# CAMERA_DVP_FPC24_OV26407670.net
KiCad netlist of a schematic drawn in Altium Designer
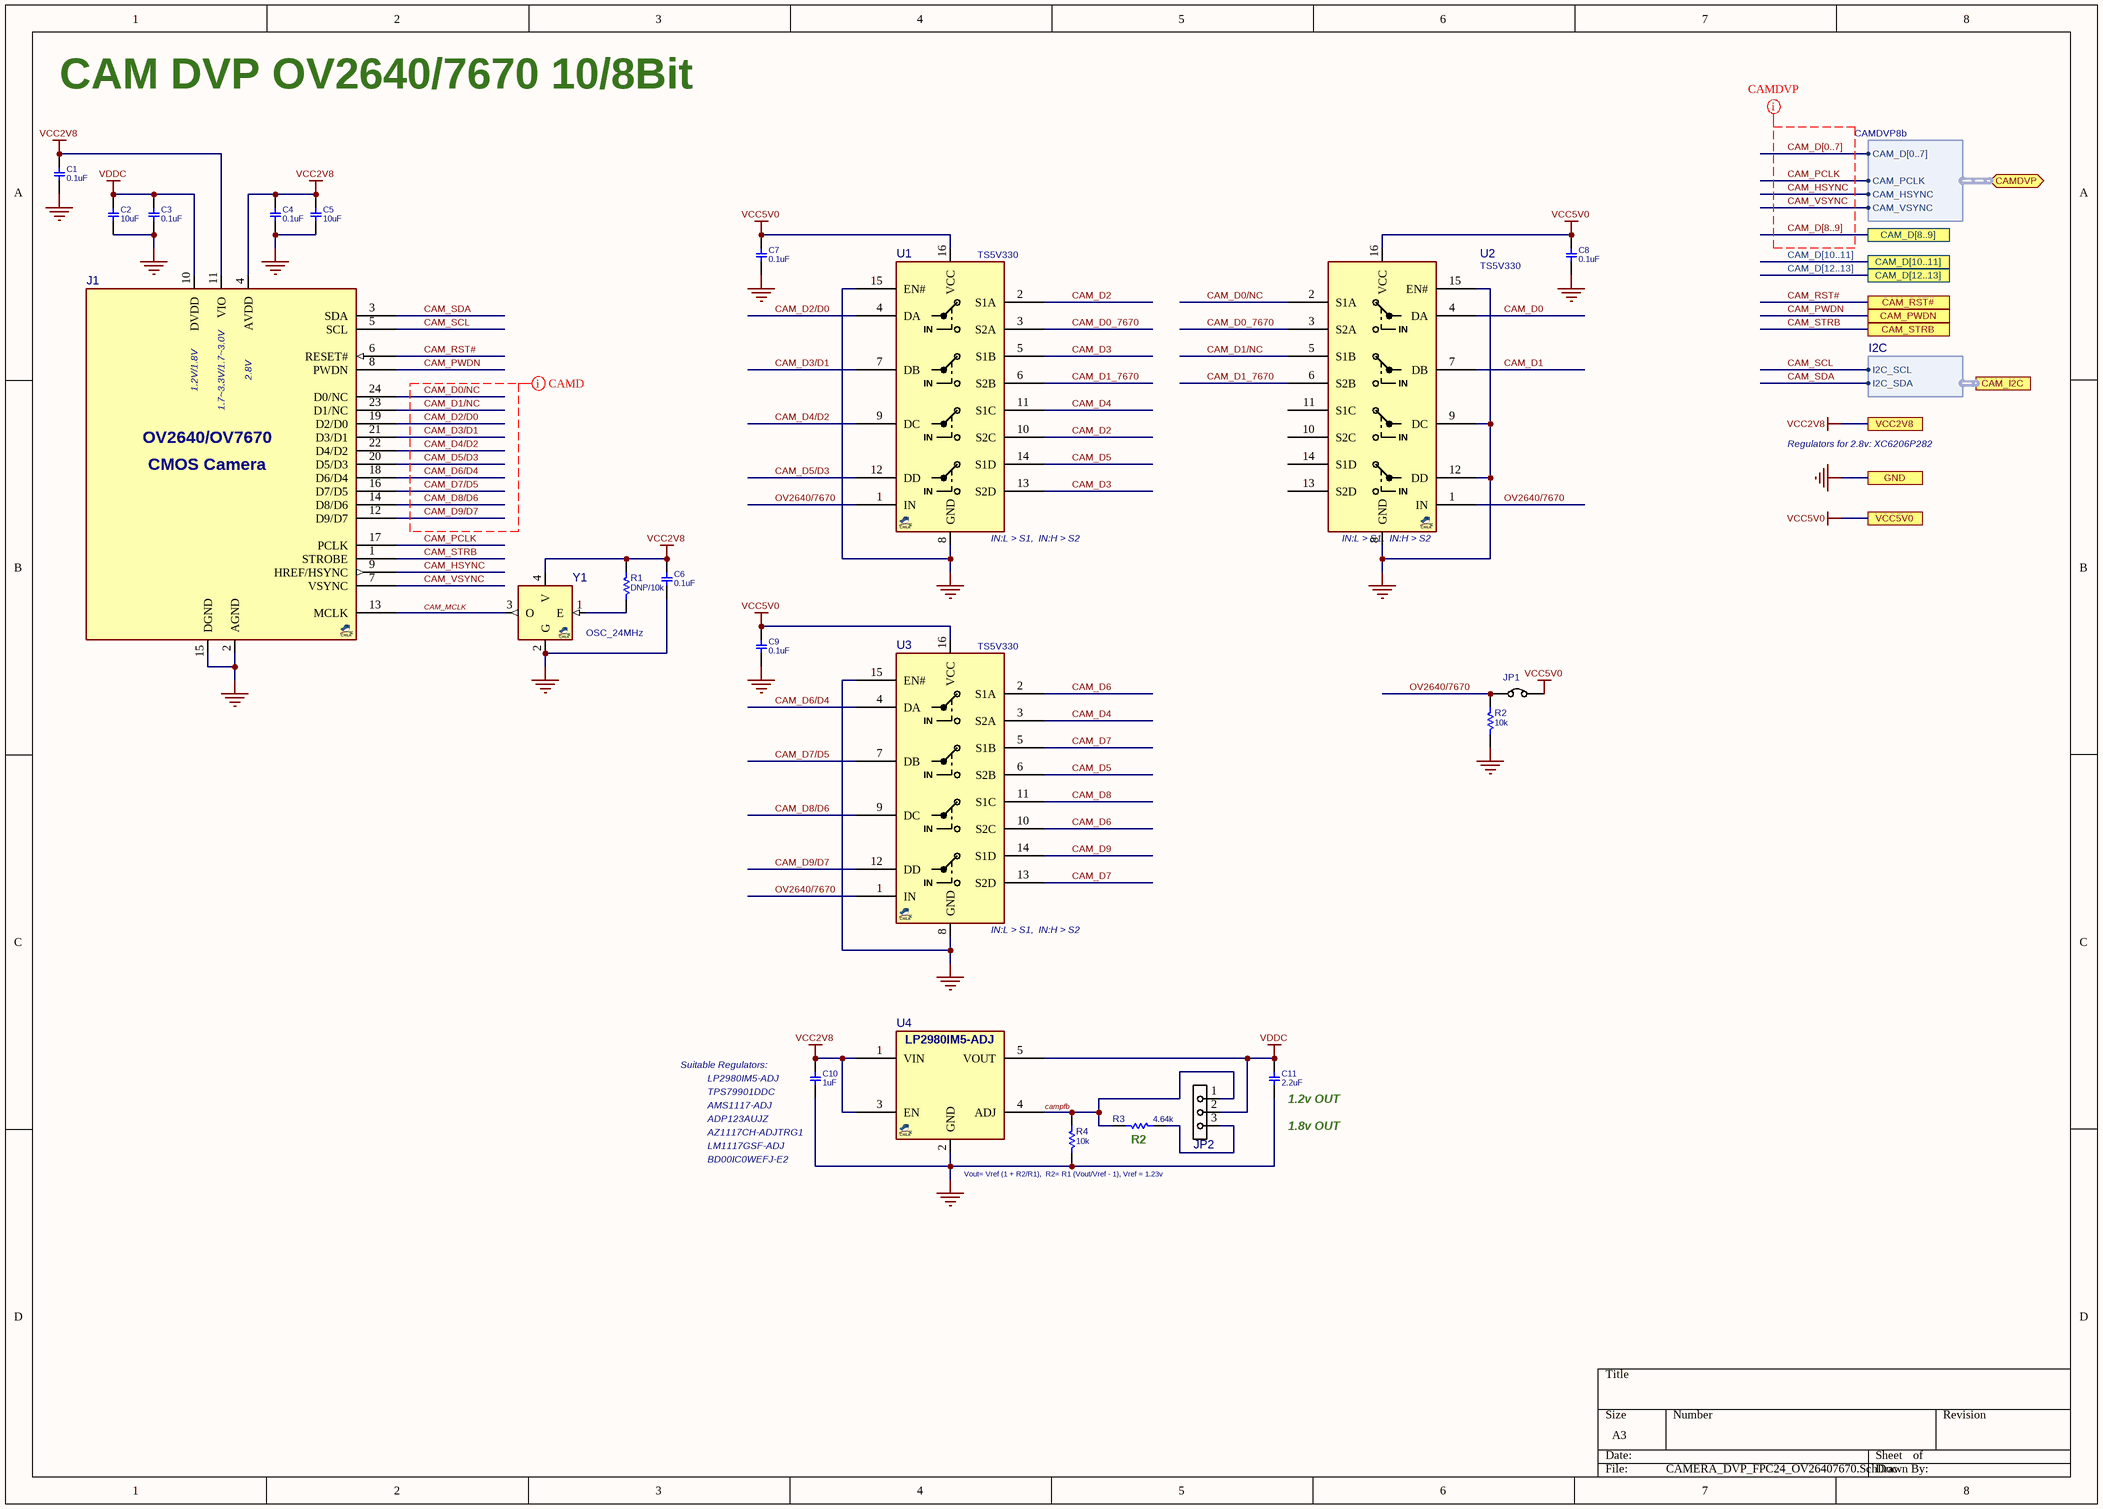
[diagram p0: CAMERA_DVP_FPC24_OV26407670.SchDoc]

(export (version "E")
  (design (tool "Eeschema 10.0.6"))
  (components
    (comp (ref "C1")
      (value "0.1uF")
      (footprint "C0402")
      (description "CAP, MLCC")
      (libsource (lib "mlcc_smd_passive") (part "CAP_SMD_MLCC_100n50TDK"))
    )
    (comp (ref "C2")
      (value "10uF")
      (footprint "C0402")
      (description "CAP, MLCC")
      (libsource (lib "mlcc_smd_passive") (part "CAP_SMD_MLCC_100n50TDK"))
    )
    (comp (ref "C3")
      (value "0.1uF")
      (footprint "C0402")
      (description "CAP, MLCC")
      (libsource (lib "mlcc_smd_passive") (part "CAP_SMD_MLCC_100n50TDK"))
    )
    (comp (ref "C4")
      (value "0.1uF")
      (footprint "C0402")
      (description "CAP, MLCC")
      (libsource (lib "mlcc_smd_passive") (part "CAP_SMD_MLCC_100n50TDK"))
    )
    (comp (ref "C5")
      (value "10uF")
      (footprint "C0402")
      (description "CAP, MLCC")
      (libsource (lib "mlcc_smd_passive") (part "CAP_SMD_MLCC_100n50TDK"))
    )
    (comp (ref "C6")
      (value "0.1uF")
      (footprint "C0402")
      (description "CAP, MLCC")
      (libsource (lib "mlcc_smd_passive") (part "CAP_SMD_MLCC_100n50TDK"))
    )
    (comp (ref "C7")
      (value "0.1uF")
      (footprint "C0402")
      (description "CAP, MLCC")
      (libsource (lib "mlcc_smd_passive") (part "CAP_SMD_MLCC_100n50TDK"))
    )
    (comp (ref "C8")
      (value "0.1uF")
      (footprint "C0402")
      (description "CAP, MLCC")
      (libsource (lib "mlcc_smd_passive") (part "CAP_SMD_MLCC_100n50TDK"))
    )
    (comp (ref "C9")
      (value "0.1uF")
      (footprint "C0402")
      (description "CAP, MLCC")
      (libsource (lib "mlcc_smd_passive") (part "CAP_SMD_MLCC_100n50TDK"))
    )
    (comp (ref "C10")
      (value "1uF")
      (footprint "C0402")
      (description "CAP, MLCC")
      (libsource (lib "mlcc_smd_passive") (part "CAP_SMD_MLCC_100n50TDK"))
    )
    (comp (ref "C11")
      (value "2.2uF")
      (footprint "C0402")
      (description "CAP, MLCC")
      (libsource (lib "mlcc_smd_passive") (part "CAP_SMD_MLCC_100n50TDK"))
    )
    (comp (ref "J1")
      (value "OV2640/7670")
      (footprint "FPC50_24")
      (description "Camera Module, Color, DVP FPC24")
      (libsource (lib "camera") (part "OV2640_7670_FPC24"))
    )
    (comp (ref "JP1")
      (value "JMPHDR2PIN")
      (footprint "JP_60X100")
      (description "JUMPER, HEADER 2PIN")
      (fields (field (name "MANF") "MANF") (field (name "MANF_P#") "MANF_P#"))
      (libsource (lib "test-tp_jumper") (part "JUMPER_HDR_2P"))
    )
    (comp (ref "JP2")
      (value "JPSOLDER")
      (footprint "JP_3_60W")
      (description "JUMPER, HEADER 3PIN")
      (fields (field (name "MANF") "MANF") (field (name "MANF_P#") "MANF_P#"))
      (libsource (lib "test-tp_jumper") (part "JUMPER_HDR_3P"))
    )
    (comp (ref "R1")
      (value "DNP/10k")
      (footprint "R0402")
      (description "RESISTOR, SMD, THICK FILM, YAGEO")
      (fields (field (name "MANF_P#") "RC0402FR-071KL") (field (name "MANF") "Yageo"))
      (libsource (lib "res_smd_Yageo0402_thickfilm") (part "RES_SMD_1K_0402YK"))
    )
    (comp (ref "R2")
      (value "10k")
      (footprint "R0402")
      (description "RESISTOR, SMD, THICK FILM, YAGEO")
      (fields (field (name "MANF_P#") "RC0402FR-071KL") (field (name "MANF") "Yageo"))
      (libsource (lib "res_smd_Yageo0402_thickfilm") (part "RES_SMD_1K_0402YK"))
    )
    (comp (ref "R3")
      (value "4.64k")
      (footprint "R0402")
      (description "RESISTOR, SMD, THICK FILM, YAGEO")
      (fields (field (name "MANF_P#") "RC0402FR-071KL") (field (name "MANF") "Yageo"))
      (libsource (lib "res_smd_Yageo0402_thickfilm") (part "RES_SMD_1K_0402YK"))
    )
    (comp (ref "R4")
      (value "10k")
      (footprint "R0402")
      (description "RESISTOR, SMD, THICK FILM, YAGEO")
      (fields (field (name "MANF_P#") "RC0402FR-071KL") (field (name "MANF") "Yageo"))
      (libsource (lib "res_smd_Yageo0402_thickfilm") (part "RES_SMD_1K_0402YK"))
    )
    (comp (ref "U1")
      (value "TS5V330")
      (footprint "SOG65_16")
      (description "IC, SWITCH, Analog, SPDT, SC-70-6")
      (fields (field (name "MANF") "TI") (field (name "MANF_P#") "TS5V330PW"))
      (libsource (lib "switch_ic_analog_mux&demux") (part "BCT4157_SC70_1"))
    )
    (comp (ref "U2")
      (value "TS5V330")
      (footprint "SOG65_16")
      (description "IC, SWITCH, Analog, SPDT, SC-70-6")
      (fields (field (name "MANF") "TI") (field (name "MANF_P#") "TS5V330PW"))
      (libsource (lib "") (part "BCT4157_SC70_1_1"))
    )
    (comp (ref "U3")
      (value "TS5V330")
      (footprint "SOG65_16")
      (description "IC, SWITCH, Analog, SPDT, SC-70-6")
      (fields (field (name "MANF") "TI") (field (name "MANF_P#") "TS5V330PW"))
      (libsource (lib "switch_ic_analog_mux&demux") (part "BCT4157_SC70_1"))
    )
    (comp (ref "U4")
      (value "LP2980IM5-ADJ")
      (footprint "SOT23_5")
      (description "REG, Linear, LDO0.12V, Adj, 50mA, VIN2.5~16V")
      (fields (field (name "MANF") "Texas Instruments"))
      (libsource (lib "pwr_reg_linear_LDO_highPSRR") (part "VREG_LP2980_SOT23"))
    )
    (comp (ref "Y1")
      (value "OSC_24MHz")
      (footprint "XTL_4_3225GEN")
      (description "CLOCK OSCILLATOR, 25MHz, 10PPM, 3.2X2.5mm")
      (fields (field (name "MANF") "ECS") (field (name "MANF_P#") "OT322524MJBA4SL"))
      (libsource (lib "crystal_osc") (part "OSC_4_25MHz_3225E"))
    )
  )
  (nets
    (net (code "7") (name "/CAM_D0") (class "Default")
      (node (ref "U2") (pin "4") (pinfunction "DA_4") (pintype "passive"))
    )
    (net (code "8") (name "/CAM_D0_7670") (class "Default")
      (node (ref "U1") (pin "3") (pinfunction "S2A_3") (pintype "passive"))
      (node (ref "U2") (pin "3") (pinfunction "S2A_3") (pintype "passive"))
    )
    (net (code "9") (name "/CAM_D0{slash}NC") (class "Default")
      (node (ref "J1") (pin "24") (pinfunction "D0/NC_24") (pintype "passive"))
      (node (ref "U2") (pin "2") (pinfunction "S1A_2") (pintype "passive"))
    )
    (net (code "10") (name "/CAM_D1") (class "Default")
      (node (ref "U2") (pin "7") (pinfunction "DB_7") (pintype "passive"))
    )
    (net (code "11") (name "/CAM_D1_7670") (class "Default")
      (node (ref "U1") (pin "6") (pinfunction "S2B_6") (pintype "passive"))
      (node (ref "U2") (pin "6") (pinfunction "S2B_6") (pintype "passive"))
    )
    (net (code "12") (name "/CAM_D1{slash}NC") (class "Default")
      (node (ref "J1") (pin "23") (pinfunction "D1/NC_23") (pintype "passive"))
      (node (ref "U2") (pin "5") (pinfunction "S1B_5") (pintype "passive"))
    )
    (net (code "13") (name "/CAM_D2") (class "Default")
      (node (ref "U1") (pin "10") (pinfunction "S2C_10") (pintype "passive"))
      (node (ref "U1") (pin "2") (pinfunction "S1A_2") (pintype "passive"))
    )
    (net (code "14") (name "/CAM_D2{slash}D0") (class "Default")
      (node (ref "J1") (pin "19") (pinfunction "D2/D0_19") (pintype "passive"))
      (node (ref "U1") (pin "4") (pinfunction "DA_4") (pintype "passive"))
    )
    (net (code "15") (name "/CAM_D3") (class "Default")
      (node (ref "U1") (pin "13") (pinfunction "S2D_13") (pintype "passive"))
      (node (ref "U1") (pin "5") (pinfunction "S1B_5") (pintype "passive"))
    )
    (net (code "16") (name "/CAM_D3{slash}D1") (class "Default")
      (node (ref "J1") (pin "21") (pinfunction "D3/D1_21") (pintype "passive"))
      (node (ref "U1") (pin "7") (pinfunction "DB_7") (pintype "passive"))
    )
    (net (code "17") (name "/CAM_D4") (class "Default")
      (node (ref "U1") (pin "11") (pinfunction "S1C_11") (pintype "passive"))
      (node (ref "U3") (pin "3") (pinfunction "S2A_3") (pintype "passive"))
    )
    (net (code "18") (name "/CAM_D4{slash}D2") (class "Default")
      (node (ref "J1") (pin "22") (pinfunction "D4/D2_22") (pintype "passive"))
      (node (ref "U1") (pin "9") (pinfunction "DC_9") (pintype "passive"))
    )
    (net (code "19") (name "/CAM_D5") (class "Default")
      (node (ref "U1") (pin "14") (pinfunction "S1D_14") (pintype "passive"))
      (node (ref "U3") (pin "6") (pinfunction "S2B_6") (pintype "passive"))
    )
    (net (code "20") (name "/CAM_D5{slash}D3") (class "Default")
      (node (ref "J1") (pin "20") (pinfunction "D5/D3_20") (pintype "passive"))
      (node (ref "U1") (pin "12") (pinfunction "DD_12") (pintype "passive"))
    )
    (net (code "21") (name "/CAM_D6") (class "Default")
      (node (ref "U3") (pin "10") (pinfunction "S2C_10") (pintype "passive"))
      (node (ref "U3") (pin "2") (pinfunction "S1A_2") (pintype "passive"))
    )
    (net (code "22") (name "/CAM_D6{slash}D4") (class "Default")
      (node (ref "J1") (pin "18") (pinfunction "D6/D4_18") (pintype "passive"))
      (node (ref "U3") (pin "4") (pinfunction "DA_4") (pintype "passive"))
    )
    (net (code "23") (name "/CAM_D7") (class "Default")
      (node (ref "U3") (pin "13") (pinfunction "S2D_13") (pintype "passive"))
      (node (ref "U3") (pin "5") (pinfunction "S1B_5") (pintype "passive"))
    )
    (net (code "24") (name "/CAM_D7{slash}D5") (class "Default")
      (node (ref "J1") (pin "16") (pinfunction "D7/D5_16") (pintype "passive"))
      (node (ref "U3") (pin "7") (pinfunction "DB_7") (pintype "passive"))
    )
    (net (code "25") (name "/CAM_D8") (class "Default")
      (node (ref "U3") (pin "11") (pinfunction "S1C_11") (pintype "passive"))
    )
    (net (code "26") (name "/CAM_D8{slash}D6") (class "Default")
      (node (ref "J1") (pin "14") (pinfunction "D8/D6_14") (pintype "passive"))
      (node (ref "U3") (pin "9") (pinfunction "DC_9") (pintype "passive"))
    )
    (net (code "27") (name "/CAM_D9") (class "Default")
      (node (ref "U3") (pin "14") (pinfunction "S1D_14") (pintype "passive"))
    )
    (net (code "28") (name "/CAM_D9{slash}D7") (class "Default")
      (node (ref "J1") (pin "12") (pinfunction "D9/D7_12") (pintype "passive"))
      (node (ref "U3") (pin "12") (pinfunction "DD_12") (pintype "passive"))
    )
    (net (code "33") (name "/CAM_HSYNC") (class "Default")
      (node (ref "J1") (pin "9") (pinfunction "HREF/HSYNC_9") (pintype "output"))
    )
    (net (code "34") (name "/CAM_MCLK") (class "Default")
      (node (ref "J1") (pin "13") (pinfunction "MCLK_13") (pintype "passive"))
      (node (ref "Y1") (pin "3") (pinfunction "O_3") (pintype "output"))
    )
    (net (code "35") (name "/CAM_PCLK") (class "Default")
      (node (ref "J1") (pin "17") (pinfunction "PCLK_17") (pintype "passive"))
    )
    (net (code "36") (name "/CAM_PWDN") (class "Default")
      (node (ref "J1") (pin "8") (pinfunction "PWDN_8") (pintype "passive"))
    )
    (net (code "37") (name "/CAM_RST#") (class "Default")
      (node (ref "J1") (pin "6") (pinfunction "RESET#_6") (pintype "input"))
    )
    (net (code "38") (name "/CAM_SCL") (class "Default")
      (node (ref "J1") (pin "5") (pinfunction "SCL_5") (pintype "passive"))
    )
    (net (code "39") (name "/CAM_SDA") (class "Default")
      (node (ref "J1") (pin "3") (pinfunction "SDA_3") (pintype "passive"))
    )
    (net (code "40") (name "/CAM_STRB") (class "Default")
      (node (ref "J1") (pin "1") (pinfunction "STROBE_1") (pintype "passive"))
    )
    (net (code "41") (name "/CAM_VSYNC") (class "Default")
      (node (ref "J1") (pin "7") (pinfunction "VSYNC_7") (pintype "passive"))
    )
    (net (code "42") (name "/OV2640{slash}7670") (class "Default")
      (node (ref "JP1") (pin "1") (pinfunction "1_1") (pintype "passive"))
      (node (ref "R2") (pin "1") (pinfunction "1_1") (pintype "passive"))
      (node (ref "U1") (pin "1") (pinfunction "IN_1") (pintype "passive"))
      (node (ref "U2") (pin "1") (pinfunction "IN_1") (pintype "passive"))
      (node (ref "U3") (pin "1") (pinfunction "IN_1") (pintype "passive"))
    )
    (net (code "43") (name "/campfb") (class "Default")
      (node (ref "JP2") (pin "1") (pinfunction "1_1") (pintype "passive"))
      (node (ref "R3") (pin "2") (pinfunction "2_2") (pintype "passive"))
      (node (ref "R4") (pin "1") (pinfunction "1_1") (pintype "passive"))
      (node (ref "U4") (pin "4") (pinfunction "ADJ_4") (pintype "passive"))
    )
    (net (code "46") (name "GND") (class "Default")
      (node (ref "C1") (pin "2") (pinfunction "2_2") (pintype "passive"))
      (node (ref "C10") (pin "2") (pinfunction "2_2") (pintype "passive"))
      (node (ref "C11") (pin "2") (pinfunction "2_2") (pintype "passive"))
      (node (ref "C2") (pin "2") (pinfunction "2_2") (pintype "passive"))
      (node (ref "C3") (pin "2") (pinfunction "2_2") (pintype "passive"))
      (node (ref "C4") (pin "2") (pinfunction "2_2") (pintype "passive"))
      (node (ref "C5") (pin "2") (pinfunction "2_2") (pintype "passive"))
      (node (ref "C6") (pin "2") (pinfunction "2_2") (pintype "passive"))
      (node (ref "C7") (pin "2") (pinfunction "2_2") (pintype "passive"))
      (node (ref "C8") (pin "2") (pinfunction "2_2") (pintype "passive"))
      (node (ref "C9") (pin "2") (pinfunction "2_2") (pintype "passive"))
      (node (ref "J1") (pin "15") (pinfunction "DGND_15") (pintype "power_in"))
      (node (ref "J1") (pin "2") (pinfunction "AGND_2") (pintype "power_in"))
      (node (ref "R2") (pin "2") (pinfunction "2_2") (pintype "passive"))
      (node (ref "R4") (pin "2") (pinfunction "2_2") (pintype "passive"))
      (node (ref "U1") (pin "15") (pinfunction "EN#_15") (pintype "passive"))
      (node (ref "U1") (pin "8") (pinfunction "GND_8") (pintype "passive"))
      (node (ref "U2") (pin "12") (pinfunction "DD_12") (pintype "passive"))
      (node (ref "U2") (pin "15") (pinfunction "EN#_15") (pintype "passive"))
      (node (ref "U2") (pin "8") (pinfunction "GND_8") (pintype "passive"))
      (node (ref "U2") (pin "9") (pinfunction "DC_9") (pintype "passive"))
      (node (ref "U3") (pin "15") (pinfunction "EN#_15") (pintype "passive"))
      (node (ref "U3") (pin "8") (pinfunction "GND_8") (pintype "passive"))
      (node (ref "U4") (pin "2") (pinfunction "GND_2") (pintype "passive"))
      (node (ref "Y1") (pin "2") (pinfunction "G_2") (pintype "power_in"))
    )
    (net (code "47") (name "Net-(JP2-Pad3)") (class "Default")
      (node (ref "JP2") (pin "3") (pinfunction "3_3") (pintype "passive"))
      (node (ref "R3") (pin "1") (pinfunction "1_1") (pintype "passive"))
    )
    (net (code "48") (name "Net-(Y1-E)") (class "Default")
      (node (ref "R1") (pin "2") (pinfunction "2_2") (pintype "passive"))
      (node (ref "Y1") (pin "1") (pinfunction "E_1") (pintype "input"))
    )
    (net (code "49") (name "VCC2V8") (class "Default")
      (node (ref "C1") (pin "1") (pinfunction "1_1") (pintype "passive"))
      (node (ref "C10") (pin "1") (pinfunction "1_1") (pintype "passive"))
      (node (ref "C4") (pin "1") (pinfunction "1_1") (pintype "passive"))
      (node (ref "C5") (pin "1") (pinfunction "1_1") (pintype "passive"))
      (node (ref "C6") (pin "1") (pinfunction "1_1") (pintype "passive"))
      (node (ref "J1") (pin "11") (pinfunction "VIO_11") (pintype "power_in"))
      (node (ref "J1") (pin "4") (pinfunction "AVDD_4") (pintype "power_in"))
      (node (ref "R1") (pin "1") (pinfunction "1_1") (pintype "passive"))
      (node (ref "U4") (pin "1") (pinfunction "VIN_1") (pintype "passive"))
      (node (ref "U4") (pin "3") (pinfunction "EN_3") (pintype "passive"))
      (node (ref "Y1") (pin "4") (pinfunction "V_4") (pintype "power_in"))
    )
    (net (code "50") (name "VCC5V0") (class "Default")
      (node (ref "C7") (pin "1") (pinfunction "1_1") (pintype "passive"))
      (node (ref "C8") (pin "1") (pinfunction "1_1") (pintype "passive"))
      (node (ref "C9") (pin "1") (pinfunction "1_1") (pintype "passive"))
      (node (ref "JP1") (pin "2") (pinfunction "2_2") (pintype "passive"))
      (node (ref "U1") (pin "16") (pinfunction "VCC_16") (pintype "passive"))
      (node (ref "U2") (pin "16") (pinfunction "VCC_16") (pintype "passive"))
      (node (ref "U3") (pin "16") (pinfunction "VCC_16") (pintype "passive"))
    )
    (net (code "51") (name "VDDC") (class "Default")
      (node (ref "C11") (pin "1") (pinfunction "1_1") (pintype "passive"))
      (node (ref "C2") (pin "1") (pinfunction "1_1") (pintype "passive"))
      (node (ref "C3") (pin "1") (pinfunction "1_1") (pintype "passive"))
      (node (ref "J1") (pin "10") (pinfunction "DVDD_10") (pintype "power_in"))
      (node (ref "JP2") (pin "2") (pinfunction "2_2") (pintype "passive"))
      (node (ref "U4") (pin "5") (pinfunction "VOUT_5") (pintype "passive"))
    )
    (net (code "52") (name "unconnected-(U2-S1C-Pad11)") (class "Default")
      (node (ref "U2") (pin "11") (pinfunction "S1C_11") (pintype "passive"))
    )
    (net (code "53") (name "unconnected-(U2-S1D-Pad14)") (class "Default")
      (node (ref "U2") (pin "14") (pinfunction "S1D_14") (pintype "passive"))
    )
    (net (code "54") (name "unconnected-(U2-S2C-Pad10)") (class "Default")
      (node (ref "U2") (pin "10") (pinfunction "S2C_10") (pintype "passive"))
    )
    (net (code "55") (name "unconnected-(U2-S2D-Pad13)") (class "Default")
      (node (ref "U2") (pin "13") (pinfunction "S2D_13") (pintype "passive"))
    )
  )
)
